# USB.net
KiCad netlist of a schematic drawn in Altium Designer
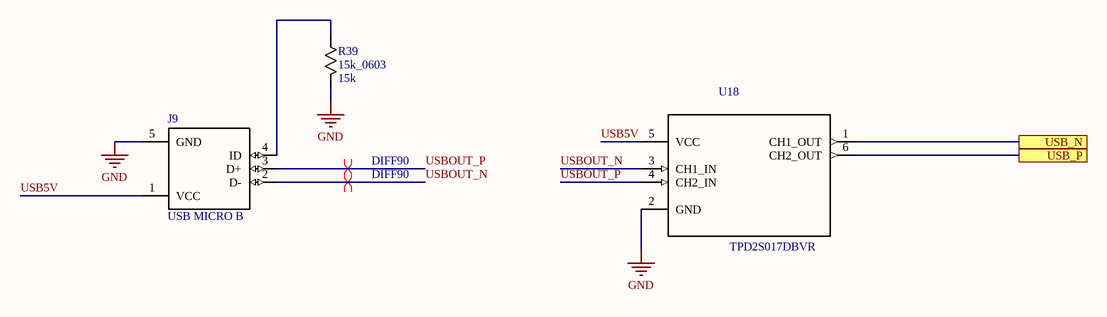
[diagram p0: USB.SchDoc]

(export (version "E")
  (design (tool "Eeschema 10.0.6"))
  (components
    (comp (ref "J9")
      (value "USB MICRO B")
      (footprint "10103594-0001LF")
      (libsource (lib "Connectors") (part "10103594-0001LF"))
    )
    (comp (ref "R39")
      (value "15k_0603")
      (footprint "0603")
      (fields
        (field (name "MANUFACTURER") "Panasonic")
        (field (name "MANUFACTURER PART NUMBER") "ERJ-3EKF1502V")
        (field (name "TOLERANCE") "1%")
        (field (name "RESISTANCE") "15k")
      )
      (libsource (lib "Resistors") (part "15k_0603"))
    )
    (comp (ref "U18")
      (value "TPD2S017DBVR")
      (footprint "SOT95P280X145-6N")
      (description "2-Channel Ultra Low Clamp Voltage ESD Solution with Series-Resistor Isolation 6-SOT-23 -40 to 85")
      (fields (field (name "MF") "Texas Instruments"))
      (libsource (lib "Diodes") (part "TPD2S017DBVR"))
    )
  )
  (nets
    (net (code "1") (name "/USB5V") (class "Default")
      (node (ref "J9") (pin "1") (pinfunction "VCC_1") (pintype "power_in"))
      (node (ref "U18") (pin "5") (pinfunction "VCC_5") (pintype "power_in"))
    )
    (net (code "2") (name "/USBOUT_N") (class "Default")
      (node (ref "J9") (pin "2") (pinfunction "D-_2") (pintype "bidirectional"))
      (node (ref "U18") (pin "3") (pinfunction "CH1_IN_3") (pintype "input"))
    )
    (net (code "3") (name "/USBOUT_P") (class "Default")
      (node (ref "J9") (pin "3") (pinfunction "D+_3") (pintype "bidirectional"))
      (node (ref "U18") (pin "4") (pinfunction "CH2_IN_4") (pintype "input"))
    )
    (net (code "4") (name "/USB_N") (class "Default")
      (node (ref "U18") (pin "1") (pinfunction "CH1_OUT_1") (pintype "output"))
    )
    (net (code "5") (name "/USB_P") (class "Default")
      (node (ref "U18") (pin "6") (pinfunction "CH2_OUT_6") (pintype "output"))
    )
    (net (code "6") (name "GND") (class "Default")
      (node (ref "J9") (pin "5") (pinfunction "GND_5") (pintype "power_in"))
      (node (ref "R39") (pin "1") (pinfunction "1_1") (pintype "passive"))
      (node (ref "U18") (pin "2") (pinfunction "GND_2") (pintype "passive"))
    )
    (net (code "7") (name "Net-(J9-ID)") (class "Default")
      (node (ref "J9") (pin "4") (pinfunction "ID_4") (pintype "bidirectional"))
      (node (ref "R39") (pin "2") (pinfunction "2_2") (pintype "passive"))
    )
  )
)
